# B210B.net
KiCad netlist of a schematic drawn in EAGLE
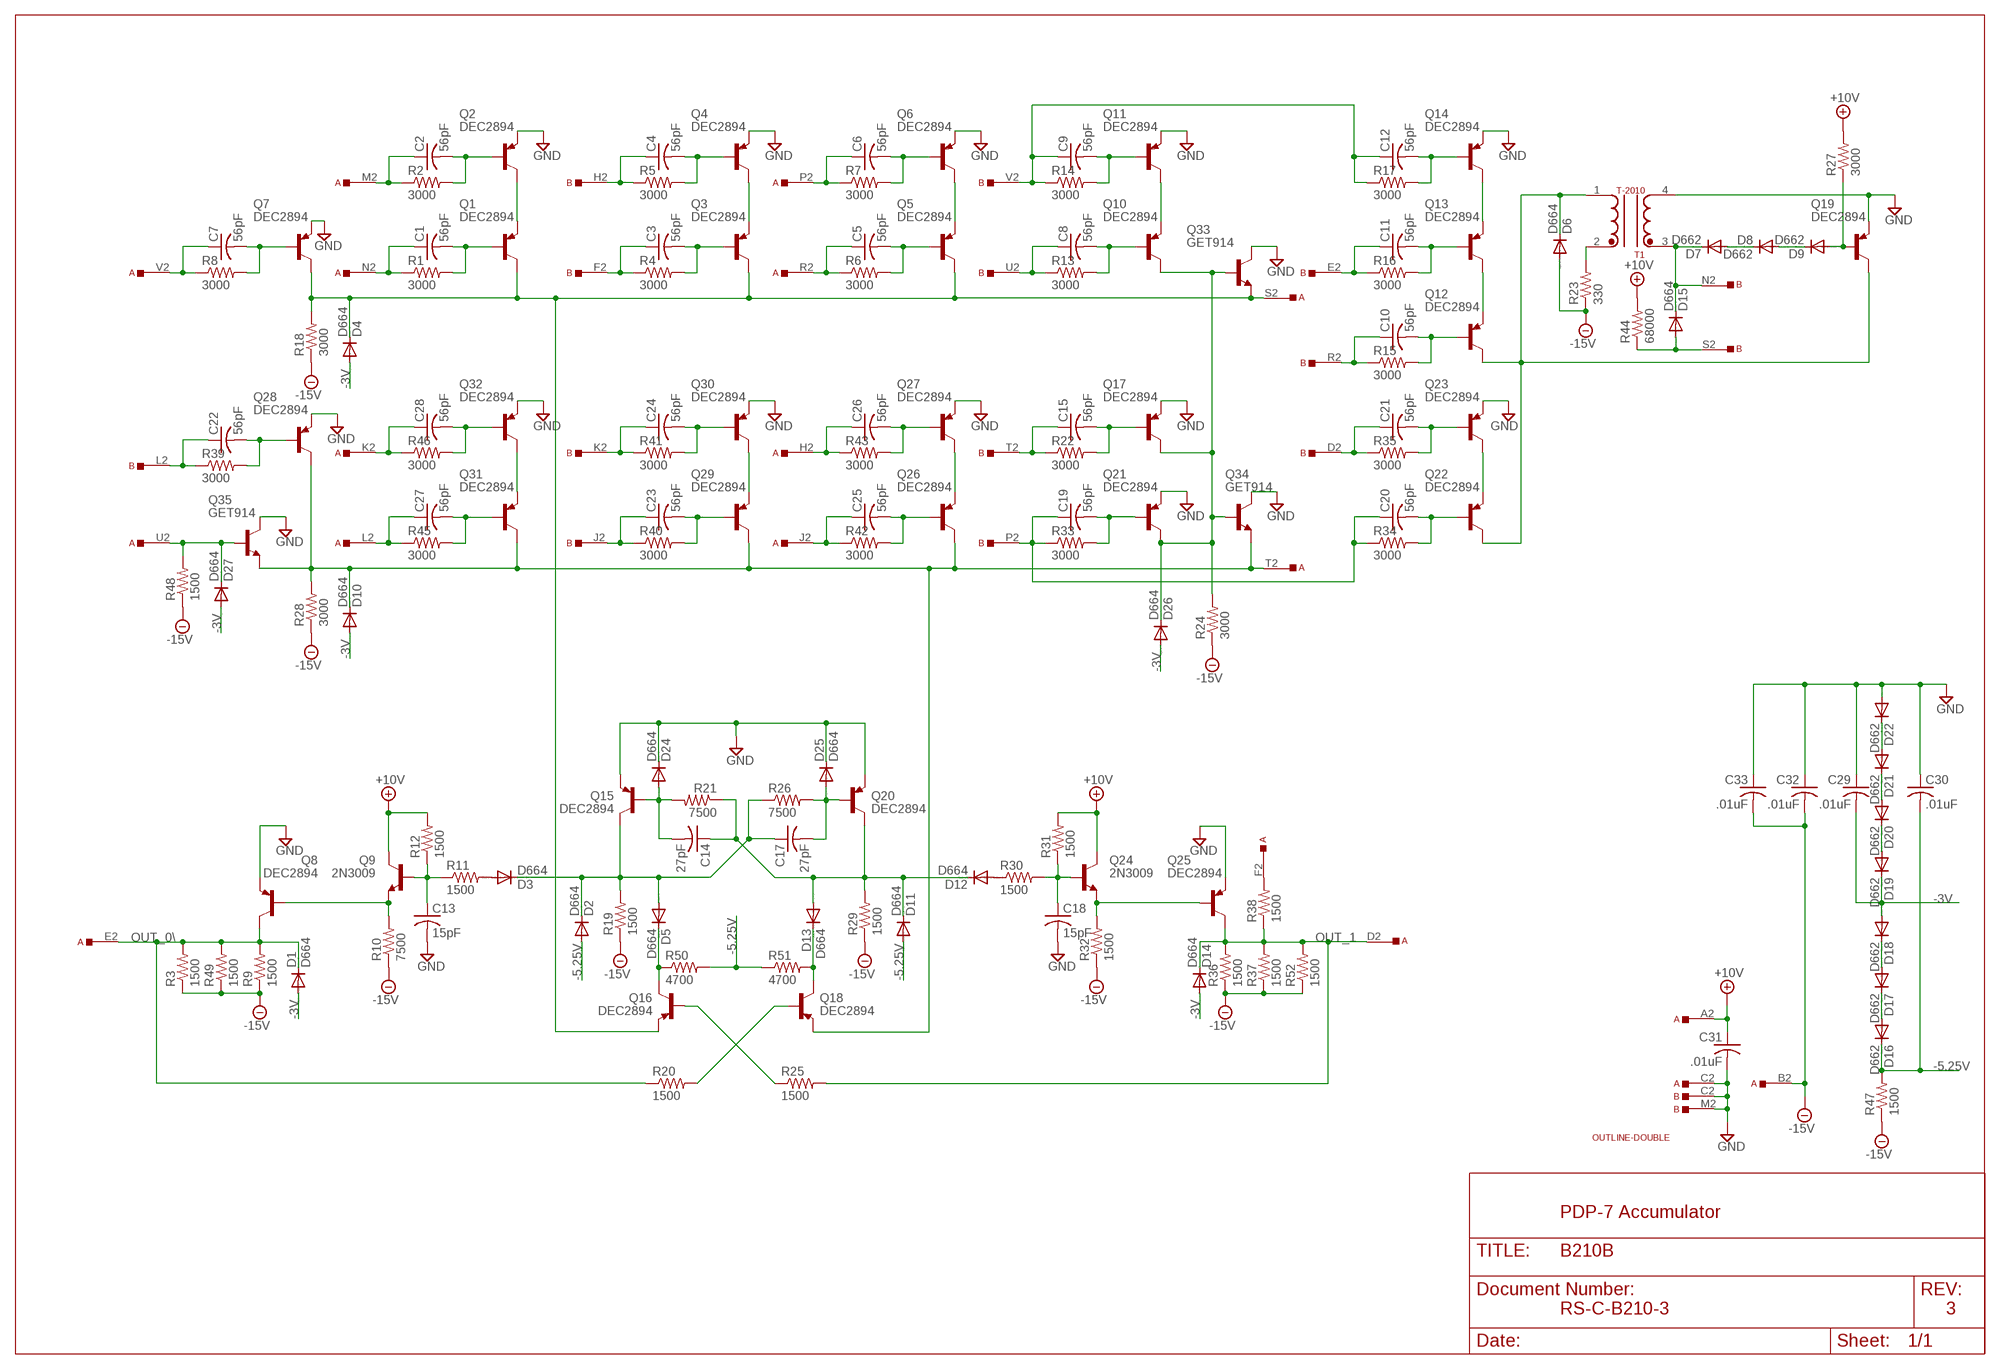
[diagram p0: schematic, sheet 1]

(export (version "E")
  (design (tool "Eeschema 10.0.6"))
  (components
    (comp (ref "A")
      (value "SS-TOP")
      (footprint "eagle-import:EDGE-CON1")
      (libsource (lib "eagle-import") (part "SS-TOP"))
    )
    (comp (ref "B")
      (value "SS-TOP")
      (footprint "eagle-import:EDGE-CON1")
      (libsource (lib "eagle-import") (part "SS-TOP"))
    )
    (comp (ref "C1")
      (value "56pF")
      (footprint "eagle-import:C063-025X075")
      (libsource (lib "eagle-import") (part "C-US"))
    )
    (comp (ref "C2")
      (value "56pF")
      (footprint "eagle-import:C063-025X075")
      (libsource (lib "eagle-import") (part "C-US"))
    )
    (comp (ref "C3")
      (value "56pF")
      (footprint "eagle-import:C063-025X075")
      (libsource (lib "eagle-import") (part "C-US"))
    )
    (comp (ref "C4")
      (value "56pF")
      (footprint "eagle-import:C063-025X075")
      (libsource (lib "eagle-import") (part "C-US"))
    )
    (comp (ref "C5")
      (value "56pF")
      (footprint "eagle-import:C063-025X075")
      (libsource (lib "eagle-import") (part "C-US"))
    )
    (comp (ref "C6")
      (value "56pF")
      (footprint "eagle-import:C063-025X075")
      (libsource (lib "eagle-import") (part "C-US"))
    )
    (comp (ref "C7")
      (value "56pF")
      (footprint "eagle-import:C063-025X075")
      (libsource (lib "eagle-import") (part "C-US"))
    )
    (comp (ref "C8")
      (value "56pF")
      (footprint "eagle-import:C063-025X075")
      (libsource (lib "eagle-import") (part "C-US"))
    )
    (comp (ref "C9")
      (value "56pF")
      (footprint "eagle-import:C063-025X075")
      (libsource (lib "eagle-import") (part "C-US"))
    )
    (comp (ref "C10")
      (value "56pF")
      (footprint "eagle-import:C063-025X075")
      (libsource (lib "eagle-import") (part "C-US"))
    )
    (comp (ref "C11")
      (value "56pF")
      (footprint "eagle-import:C063-025X075")
      (libsource (lib "eagle-import") (part "C-US"))
    )
    (comp (ref "C12")
      (value "56pF")
      (footprint "eagle-import:C063-025X075")
      (libsource (lib "eagle-import") (part "C-US"))
    )
    (comp (ref "C13")
      (value "15pF")
      (footprint "eagle-import:C063-025X075")
      (libsource (lib "eagle-import") (part "C-US"))
    )
    (comp (ref "C14")
      (value "27pF")
      (footprint "eagle-import:C063-025X075")
      (libsource (lib "eagle-import") (part "C-US"))
    )
    (comp (ref "C15")
      (value "56pF")
      (footprint "eagle-import:C063-025X075")
      (libsource (lib "eagle-import") (part "C-US"))
    )
    (comp (ref "C17")
      (value "27pF")
      (footprint "eagle-import:C063-025X075")
      (libsource (lib "eagle-import") (part "C-US"))
    )
    (comp (ref "C18")
      (value "15pF")
      (footprint "eagle-import:C063-025X075")
      (libsource (lib "eagle-import") (part "C-US"))
    )
    (comp (ref "C19")
      (value "56pF")
      (footprint "eagle-import:C063-025X075")
      (libsource (lib "eagle-import") (part "C-US"))
    )
    (comp (ref "C20")
      (value "56pF")
      (footprint "eagle-import:C063-025X075")
      (libsource (lib "eagle-import") (part "C-US"))
    )
    (comp (ref "C21")
      (value "56pF")
      (footprint "eagle-import:C063-025X075")
      (libsource (lib "eagle-import") (part "C-US"))
    )
    (comp (ref "C22")
      (value "56pF")
      (footprint "eagle-import:C063-025X075")
      (libsource (lib "eagle-import") (part "C-US"))
    )
    (comp (ref "C23")
      (value "56pF")
      (footprint "eagle-import:C063-025X075")
      (libsource (lib "eagle-import") (part "C-US"))
    )
    (comp (ref "C24")
      (value "56pF")
      (footprint "eagle-import:C063-025X075")
      (libsource (lib "eagle-import") (part "C-US"))
    )
    (comp (ref "C25")
      (value "56pF")
      (footprint "eagle-import:C063-025X075")
      (libsource (lib "eagle-import") (part "C-US"))
    )
    (comp (ref "C26")
      (value "56pF")
      (footprint "eagle-import:C063-025X075")
      (libsource (lib "eagle-import") (part "C-US"))
    )
    (comp (ref "C27")
      (value "56pF")
      (footprint "eagle-import:C063-025X075")
      (libsource (lib "eagle-import") (part "C-US"))
    )
    (comp (ref "C28")
      (value "56pF")
      (footprint "eagle-import:C063-025X075")
      (libsource (lib "eagle-import") (part "C-US"))
    )
    (comp (ref "C29")
      (value ".01uF")
      (footprint "eagle-import:C063-025X075")
      (libsource (lib "eagle-import") (part "C-US"))
    )
    (comp (ref "C30")
      (value ".01uF")
      (footprint "eagle-import:C063-025X075")
      (libsource (lib "eagle-import") (part "C-US"))
    )
    (comp (ref "C31")
      (value ".01uF")
      (footprint "eagle-import:C063-025X075")
      (libsource (lib "eagle-import") (part "C-US"))
    )
    (comp (ref "C32")
      (value ".01uF")
      (footprint "eagle-import:C063-025X075")
      (libsource (lib "eagle-import") (part "C-US"))
    )
    (comp (ref "C33")
      (value ".01uF")
      (footprint "eagle-import:C063-025X075")
      (libsource (lib "eagle-import") (part "C-US"))
    )
    (comp (ref "D1")
      (value "D664")
      (footprint "eagle-import:DO35-10")
      (libsource (lib "eagle-import") (part "DIODE-DO35-10"))
    )
    (comp (ref "D2")
      (value "D664")
      (footprint "eagle-import:DO35-10")
      (libsource (lib "eagle-import") (part "DIODE-DO35-10"))
    )
    (comp (ref "D3")
      (value "D664")
      (footprint "eagle-import:DO35-10")
      (libsource (lib "eagle-import") (part "DIODE-DO35-10"))
    )
    (comp (ref "D4")
      (value "D664")
      (footprint "eagle-import:DO35-10")
      (libsource (lib "eagle-import") (part "DIODE-DO35-10"))
    )
    (comp (ref "D5")
      (value "D664")
      (footprint "eagle-import:DO35-10")
      (libsource (lib "eagle-import") (part "DIODE-DO35-10"))
    )
    (comp (ref "D6")
      (value "D664")
      (footprint "eagle-import:DO35-10")
      (libsource (lib "eagle-import") (part "DIODE-DO35-10"))
    )
    (comp (ref "D7")
      (value "D662")
      (footprint "eagle-import:DO35-10")
      (libsource (lib "eagle-import") (part "DIODE-DO35-10"))
    )
    (comp (ref "D8")
      (value "D662")
      (footprint "eagle-import:DO35-10")
      (libsource (lib "eagle-import") (part "DIODE-DO35-10"))
    )
    (comp (ref "D9")
      (value "D662")
      (footprint "eagle-import:DO35-10")
      (libsource (lib "eagle-import") (part "DIODE-DO35-10"))
    )
    (comp (ref "D10")
      (value "D664")
      (footprint "eagle-import:DO35-10")
      (libsource (lib "eagle-import") (part "DIODE-DO35-10"))
    )
    (comp (ref "D11")
      (value "D664")
      (footprint "eagle-import:DO35-10")
      (libsource (lib "eagle-import") (part "DIODE-DO35-10"))
    )
    (comp (ref "D12")
      (value "D664")
      (footprint "eagle-import:DO35-10")
      (libsource (lib "eagle-import") (part "DIODE-DO35-10"))
    )
    (comp (ref "D13")
      (value "D664")
      (footprint "eagle-import:DO35-10")
      (libsource (lib "eagle-import") (part "DIODE-DO35-10"))
    )
    (comp (ref "D14")
      (value "D664")
      (footprint "eagle-import:DO35-10")
      (libsource (lib "eagle-import") (part "DIODE-DO35-10"))
    )
    (comp (ref "D15")
      (value "D664")
      (footprint "eagle-import:DO35-10")
      (libsource (lib "eagle-import") (part "DIODE-DO35-10"))
    )
    (comp (ref "D16")
      (value "D662")
      (footprint "eagle-import:DO35-10")
      (libsource (lib "eagle-import") (part "DIODE-DO35-10"))
    )
    (comp (ref "D17")
      (value "D662")
      (footprint "eagle-import:DO35-10")
      (libsource (lib "eagle-import") (part "DIODE-DO35-10"))
    )
    (comp (ref "D18")
      (value "D662")
      (footprint "eagle-import:DO35-10")
      (libsource (lib "eagle-import") (part "DIODE-DO35-10"))
    )
    (comp (ref "D19")
      (value "D662")
      (footprint "eagle-import:DO35-10")
      (libsource (lib "eagle-import") (part "DIODE-DO35-10"))
    )
    (comp (ref "D20")
      (value "D662")
      (footprint "eagle-import:DO35-10")
      (libsource (lib "eagle-import") (part "DIODE-DO35-10"))
    )
    (comp (ref "D21")
      (value "D662")
      (footprint "eagle-import:DO35-10")
      (libsource (lib "eagle-import") (part "DIODE-DO35-10"))
    )
    (comp (ref "D22")
      (value "D662")
      (footprint "eagle-import:DO35-10")
      (libsource (lib "eagle-import") (part "DIODE-DO35-10"))
    )
    (comp (ref "D24")
      (value "D664")
      (footprint "eagle-import:DO35-10")
      (libsource (lib "eagle-import") (part "DIODE-DO35-10"))
    )
    (comp (ref "D25")
      (value "D664")
      (footprint "eagle-import:DO35-10")
      (libsource (lib "eagle-import") (part "DIODE-DO35-10"))
    )
    (comp (ref "D26")
      (value "D664")
      (footprint "eagle-import:DO35-10")
      (libsource (lib "eagle-import") (part "DIODE-DO35-10"))
    )
    (comp (ref "D27")
      (value "D664")
      (footprint "eagle-import:DO35-10")
      (libsource (lib "eagle-import") (part "DIODE-DO35-10"))
    )
    (comp (ref "Q1")
      (value "DEC2894")
      (footprint "eagle-import:TO5")
      (libsource (lib "eagle-import") (part "-PNP-TO5"))
    )
    (comp (ref "Q2")
      (value "DEC2894")
      (footprint "eagle-import:TO5")
      (libsource (lib "eagle-import") (part "-PNP-TO5"))
    )
    (comp (ref "Q3")
      (value "DEC2894")
      (footprint "eagle-import:TO5")
      (libsource (lib "eagle-import") (part "-PNP-TO5"))
    )
    (comp (ref "Q4")
      (value "DEC2894")
      (footprint "eagle-import:TO5")
      (libsource (lib "eagle-import") (part "-PNP-TO5"))
    )
    (comp (ref "Q5")
      (value "DEC2894")
      (footprint "eagle-import:TO5")
      (libsource (lib "eagle-import") (part "-PNP-TO5"))
    )
    (comp (ref "Q6")
      (value "DEC2894")
      (footprint "eagle-import:TO5")
      (libsource (lib "eagle-import") (part "-PNP-TO5"))
    )
    (comp (ref "Q7")
      (value "DEC2894")
      (footprint "eagle-import:TO5")
      (libsource (lib "eagle-import") (part "-PNP-TO5"))
    )
    (comp (ref "Q8")
      (value "DEC2894")
      (footprint "eagle-import:TO5")
      (libsource (lib "eagle-import") (part "-PNP-TO5"))
    )
    (comp (ref "Q9")
      (value "2N3009")
      (footprint "eagle-import:TO5")
      (libsource (lib "eagle-import") (part "-NPN-TO5"))
    )
    (comp (ref "Q10")
      (value "DEC2894")
      (footprint "eagle-import:TO5")
      (libsource (lib "eagle-import") (part "-PNP-TO5"))
    )
    (comp (ref "Q11")
      (value "DEC2894")
      (footprint "eagle-import:TO5")
      (libsource (lib "eagle-import") (part "-PNP-TO5"))
    )
    (comp (ref "Q12")
      (value "DEC2894")
      (footprint "eagle-import:TO5")
      (libsource (lib "eagle-import") (part "-PNP-TO5"))
    )
    (comp (ref "Q13")
      (value "DEC2894")
      (footprint "eagle-import:TO5")
      (libsource (lib "eagle-import") (part "-PNP-TO5"))
    )
    (comp (ref "Q14")
      (value "DEC2894")
      (footprint "eagle-import:TO5")
      (libsource (lib "eagle-import") (part "-PNP-TO5"))
    )
    (comp (ref "Q15")
      (value "DEC2894")
      (footprint "eagle-import:TO5")
      (libsource (lib "eagle-import") (part "-PNP-TO5"))
    )
    (comp (ref "Q16")
      (value "DEC2894")
      (footprint "eagle-import:TO5")
      (libsource (lib "eagle-import") (part "-PNP-TO5"))
    )
    (comp (ref "Q17")
      (value "DEC2894")
      (footprint "eagle-import:TO5")
      (libsource (lib "eagle-import") (part "-PNP-TO5"))
    )
    (comp (ref "Q18")
      (value "DEC2894")
      (footprint "eagle-import:TO5")
      (libsource (lib "eagle-import") (part "-PNP-TO5"))
    )
    (comp (ref "Q19")
      (value "DEC2894")
      (footprint "eagle-import:TO5")
      (libsource (lib "eagle-import") (part "-PNP-TO5"))
    )
    (comp (ref "Q20")
      (value "DEC2894")
      (footprint "eagle-import:TO5")
      (libsource (lib "eagle-import") (part "-PNP-TO5"))
    )
    (comp (ref "Q21")
      (value "DEC2894")
      (footprint "eagle-import:TO5")
      (libsource (lib "eagle-import") (part "-PNP-TO5"))
    )
    (comp (ref "Q22")
      (value "DEC2894")
      (footprint "eagle-import:TO5")
      (libsource (lib "eagle-import") (part "-PNP-TO5"))
    )
    (comp (ref "Q23")
      (value "DEC2894")
      (footprint "eagle-import:TO5")
      (libsource (lib "eagle-import") (part "-PNP-TO5"))
    )
    (comp (ref "Q24")
      (value "2N3009")
      (footprint "eagle-import:TO5")
      (libsource (lib "eagle-import") (part "-NPN-TO5"))
    )
    (comp (ref "Q25")
      (value "DEC2894")
      (footprint "eagle-import:TO5")
      (libsource (lib "eagle-import") (part "-PNP-TO5"))
    )
    (comp (ref "Q26")
      (value "DEC2894")
      (footprint "eagle-import:TO5")
      (libsource (lib "eagle-import") (part "-PNP-TO5"))
    )
    (comp (ref "Q27")
      (value "DEC2894")
      (footprint "eagle-import:TO5")
      (libsource (lib "eagle-import") (part "-PNP-TO5"))
    )
    (comp (ref "Q28")
      (value "DEC2894")
      (footprint "eagle-import:TO5")
      (libsource (lib "eagle-import") (part "-PNP-TO5"))
    )
    (comp (ref "Q29")
      (value "DEC2894")
      (footprint "eagle-import:TO5")
      (libsource (lib "eagle-import") (part "-PNP-TO5"))
    )
    (comp (ref "Q30")
      (value "DEC2894")
      (footprint "eagle-import:TO5")
      (libsource (lib "eagle-import") (part "-PNP-TO5"))
    )
    (comp (ref "Q31")
      (value "DEC2894")
      (footprint "eagle-import:TO5")
      (libsource (lib "eagle-import") (part "-PNP-TO5"))
    )
    (comp (ref "Q32")
      (value "DEC2894")
      (footprint "eagle-import:TO5")
      (libsource (lib "eagle-import") (part "-PNP-TO5"))
    )
    (comp (ref "Q33")
      (value "GET914")
      (footprint "eagle-import:TO5")
      (libsource (lib "eagle-import") (part "-NPN-TO5"))
    )
    (comp (ref "Q34")
      (value "GET914")
      (footprint "eagle-import:TO5")
      (libsource (lib "eagle-import") (part "-NPN-TO5"))
    )
    (comp (ref "Q35")
      (value "GET914")
      (footprint "eagle-import:TO5")
      (libsource (lib "eagle-import") (part "-NPN-TO5"))
    )
    (comp (ref "R1")
      (value "3000")
      (footprint "eagle-import:0207_10")
      (libsource (lib "eagle-import") (part "R-US_0207/10"))
    )
    (comp (ref "R2")
      (value "3000")
      (footprint "eagle-import:0207_10")
      (libsource (lib "eagle-import") (part "R-US_0207/10"))
    )
    (comp (ref "R3")
      (value "1500")
      (footprint "eagle-import:0207_10")
      (libsource (lib "eagle-import") (part "R-US_0207/10"))
    )
    (comp (ref "R4")
      (value "3000")
      (footprint "eagle-import:0207_10")
      (libsource (lib "eagle-import") (part "R-US_0207/10"))
    )
    (comp (ref "R5")
      (value "3000")
      (footprint "eagle-import:0207_10")
      (libsource (lib "eagle-import") (part "R-US_0207/10"))
    )
    (comp (ref "R6")
      (value "3000")
      (footprint "eagle-import:0207_10")
      (libsource (lib "eagle-import") (part "R-US_0207/10"))
    )
    (comp (ref "R7")
      (value "3000")
      (footprint "eagle-import:0207_10")
      (libsource (lib "eagle-import") (part "R-US_0207/10"))
    )
    (comp (ref "R8")
      (value "3000")
      (footprint "eagle-import:0207_10")
      (libsource (lib "eagle-import") (part "R-US_0207/10"))
    )
    (comp (ref "R9")
      (value "1500")
      (footprint "eagle-import:0207_10")
      (libsource (lib "eagle-import") (part "R-US_0207/10"))
    )
    (comp (ref "R10")
      (value "7500")
      (footprint "eagle-import:0207_10")
      (libsource (lib "eagle-import") (part "R-US_0207/10"))
    )
    (comp (ref "R11")
      (value "1500")
      (footprint "eagle-import:0207_10")
      (libsource (lib "eagle-import") (part "R-US_0207/10"))
    )
    (comp (ref "R12")
      (value "1500")
      (footprint "eagle-import:0207_10")
      (libsource (lib "eagle-import") (part "R-US_0207/10"))
    )
    (comp (ref "R13")
      (value "3000")
      (footprint "eagle-import:0207_10")
      (libsource (lib "eagle-import") (part "R-US_0207/10"))
    )
    (comp (ref "R14")
      (value "3000")
      (footprint "eagle-import:0207_10")
      (libsource (lib "eagle-import") (part "R-US_0207/10"))
    )
    (comp (ref "R15")
      (value "3000")
      (footprint "eagle-import:0207_10")
      (libsource (lib "eagle-import") (part "R-US_0207/10"))
    )
    (comp (ref "R16")
      (value "3000")
      (footprint "eagle-import:0207_10")
      (libsource (lib "eagle-import") (part "R-US_0207/10"))
    )
    (comp (ref "R17")
      (value "3000")
      (footprint "eagle-import:0207_10")
      (libsource (lib "eagle-import") (part "R-US_0207/10"))
    )
    (comp (ref "R18")
      (value "3000")
      (footprint "eagle-import:0207_10")
      (libsource (lib "eagle-import") (part "R-US_0207/10"))
    )
    (comp (ref "R19")
      (value "1500")
      (footprint "eagle-import:0207_10")
      (libsource (lib "eagle-import") (part "R-US_0207/10"))
    )
    (comp (ref "R20")
      (value "1500")
      (footprint "eagle-import:0207_10")
      (libsource (lib "eagle-import") (part "R-US_0207/10"))
    )
    (comp (ref "R21")
      (value "7500")
      (footprint "eagle-import:0207_10")
      (libsource (lib "eagle-import") (part "R-US_0207/10"))
    )
    (comp (ref "R22")
      (value "3000")
      (footprint "eagle-import:0207_10")
      (libsource (lib "eagle-import") (part "R-US_0207/10"))
    )
    (comp (ref "R23")
      (value "330")
      (footprint "eagle-import:0207_10")
      (libsource (lib "eagle-import") (part "R-US_0207/10"))
    )
    (comp (ref "R24")
      (value "3000")
      (footprint "eagle-import:0207_10")
      (libsource (lib "eagle-import") (part "R-US_0207/10"))
    )
    (comp (ref "R25")
      (value "1500")
      (footprint "eagle-import:0207_10")
      (libsource (lib "eagle-import") (part "R-US_0207/10"))
    )
    (comp (ref "R26")
      (value "7500")
      (footprint "eagle-import:0207_10")
      (libsource (lib "eagle-import") (part "R-US_0207/10"))
    )
    (comp (ref "R27")
      (value "3000")
      (footprint "eagle-import:0207_10")
      (libsource (lib "eagle-import") (part "R-US_0207/10"))
    )
    (comp (ref "R28")
      (value "3000")
      (footprint "eagle-import:0207_10")
      (libsource (lib "eagle-import") (part "R-US_0207/10"))
    )
    (comp (ref "R29")
      (value "1500")
      (footprint "eagle-import:0207_10")
      (libsource (lib "eagle-import") (part "R-US_0207/10"))
    )
    (comp (ref "R30")
      (value "1500")
      (footprint "eagle-import:0207_10")
      (libsource (lib "eagle-import") (part "R-US_0207/10"))
    )
    (comp (ref "R31")
      (value "1500")
      (footprint "eagle-import:0207_10")
      (libsource (lib "eagle-import") (part "R-US_0207/10"))
    )
    (comp (ref "R32")
      (value "1500")
      (footprint "eagle-import:0207_10")
      (libsource (lib "eagle-import") (part "R-US_0207/10"))
    )
    (comp (ref "R33")
      (value "3000")
      (footprint "eagle-import:0207_10")
      (libsource (lib "eagle-import") (part "R-US_0207/10"))
    )
    (comp (ref "R34")
      (value "3000")
      (footprint "eagle-import:0207_10")
      (libsource (lib "eagle-import") (part "R-US_0207/10"))
    )
    (comp (ref "R35")
      (value "3000")
      (footprint "eagle-import:0207_10")
      (libsource (lib "eagle-import") (part "R-US_0207/10"))
    )
    (comp (ref "R36")
      (value "1500")
      (footprint "eagle-import:0207_10")
      (libsource (lib "eagle-import") (part "R-US_0207/10"))
    )
    (comp (ref "R37")
      (value "1500")
      (footprint "eagle-import:0207_10")
      (libsource (lib "eagle-import") (part "R-US_0207/10"))
    )
    (comp (ref "R38")
      (value "1500")
      (footprint "eagle-import:0207_10")
      (libsource (lib "eagle-import") (part "R-US_0207/10"))
    )
    (comp (ref "R39")
      (value "3000")
      (footprint "eagle-import:0207_10")
      (libsource (lib "eagle-import") (part "R-US_0207/10"))
    )
    (comp (ref "R40")
      (value "3000")
      (footprint "eagle-import:0207_10")
      (libsource (lib "eagle-import") (part "R-US_0207/10"))
    )
    (comp (ref "R41")
      (value "3000")
      (footprint "eagle-import:0207_10")
      (libsource (lib "eagle-import") (part "R-US_0207/10"))
    )
    (comp (ref "R42")
      (value "3000")
      (footprint "eagle-import:0207_10")
      (libsource (lib "eagle-import") (part "R-US_0207/10"))
    )
    (comp (ref "R43")
      (value "3000")
      (footprint "eagle-import:0207_10")
      (libsource (lib "eagle-import") (part "R-US_0207/10"))
    )
    (comp (ref "R44")
      (value "68000")
      (footprint "eagle-import:0207_10")
      (libsource (lib "eagle-import") (part "R-US_0207/10"))
    )
    (comp (ref "R45")
      (value "3000")
      (footprint "eagle-import:0207_10")
      (libsource (lib "eagle-import") (part "R-US_0207/10"))
    )
    (comp (ref "R46")
      (value "3000")
      (footprint "eagle-import:0207_10")
      (libsource (lib "eagle-import") (part "R-US_0207/10"))
    )
    (comp (ref "R47")
      (value "1500")
      (footprint "eagle-import:0207_10")
      (libsource (lib "eagle-import") (part "R-US_0207/10"))
    )
    (comp (ref "R48")
      (value "1500")
      (footprint "eagle-import:0207_10")
      (libsource (lib "eagle-import") (part "R-US_0207/10"))
    )
    (comp (ref "R49")
      (value "1500")
      (footprint "eagle-import:0207_10")
      (libsource (lib "eagle-import") (part "R-US_0207/10"))
    )
    (comp (ref "R50")
      (value "4700")
      (footprint "eagle-import:0207_10")
      (libsource (lib "eagle-import") (part "R-US_0207/10"))
    )
    (comp (ref "R51")
      (value "4700")
      (footprint "eagle-import:0207_10")
      (libsource (lib "eagle-import") (part "R-US_0207/10"))
    )
    (comp (ref "R52")
      (value "1500")
      (footprint "eagle-import:0207_10")
      (libsource (lib "eagle-import") (part "R-US_0207/10"))
    )
    (comp (ref "T1")
      (value "T-2010")
      (footprint "eagle-import:TRANSFORMER2")
      (libsource (lib "eagle-import") (part "T-2010"))
    )
    (comp (ref "U$1")
      (value "OUTLINE-DOUBLE")
      (footprint "eagle-import:DOUBLE")
      (libsource (lib "eagle-import") (part "OUTLINE-DOUBLE"))
    )
  )
  (nets
    (net (code "1") (name "+10V") (class "Default")
      (node (ref "A") (pin "A2") (pinfunction "P_A2") (pintype "passive"))
      (node (ref "C31") (pin "1") (pinfunction "1_1") (pintype "passive"))
      (node (ref "Q24") (pin "3") (pinfunction "C_3") (pintype "passive"))
      (node (ref "Q9") (pin "3") (pinfunction "C_3") (pintype "passive"))
      (node (ref "R12") (pin "2") (pinfunction "2_2") (pintype "passive"))
      (node (ref "R27") (pin "2") (pinfunction "2_2") (pintype "passive"))
      (node (ref "R31") (pin "2") (pinfunction "2_2") (pintype "passive"))
      (node (ref "R44") (pin "2") (pinfunction "2_2") (pintype "passive"))
    )
    (net (code "2") (name "-15V") (class "Default")
      (node (ref "A") (pin "B2") (pinfunction "P_B2") (pintype "passive"))
      (node (ref "C32") (pin "2") (pinfunction "2_2") (pintype "passive"))
      (node (ref "C33") (pin "2") (pinfunction "2_2") (pintype "passive"))
      (node (ref "D6") (pin "A") (pinfunction "A_A") (pintype "passive"))
      (node (ref "R10") (pin "1") (pinfunction "1_1") (pintype "passive"))
      (node (ref "R18") (pin "1") (pinfunction "1_1") (pintype "passive"))
      (node (ref "R19") (pin "1") (pinfunction "1_1") (pintype "passive"))
      (node (ref "R23") (pin "1") (pinfunction "1_1") (pintype "passive"))
      (node (ref "R24") (pin "1") (pinfunction "1_1") (pintype "passive"))
      (node (ref "R28") (pin "1") (pinfunction "1_1") (pintype "passive"))
      (node (ref "R29") (pin "1") (pinfunction "1_1") (pintype "passive"))
      (node (ref "R3") (pin "1") (pinfunction "1_1") (pintype "passive"))
      (node (ref "R32") (pin "1") (pinfunction "1_1") (pintype "passive"))
      (node (ref "R36") (pin "1") (pinfunction "1_1") (pintype "passive"))
      (node (ref "R37") (pin "1") (pinfunction "1_1") (pintype "passive"))
      (node (ref "R47") (pin "1") (pinfunction "1_1") (pintype "passive"))
      (node (ref "R48") (pin "1") (pinfunction "1_1") (pintype "passive"))
      (node (ref "R49") (pin "1") (pinfunction "1_1") (pintype "passive"))
      (node (ref "R52") (pin "1") (pinfunction "1_1") (pintype "passive"))
      (node (ref "R9") (pin "1") (pinfunction "1_1") (pintype "passive"))
    )
    (net (code "3") (name "/-3V") (class "Default")
      (node (ref "C29") (pin "2") (pinfunction "2_2") (pintype "passive"))
      (node (ref "D1") (pin "A") (pinfunction "A_A") (pintype "passive"))
      (node (ref "D10") (pin "A") (pinfunction "A_A") (pintype "passive"))
      (node (ref "D14") (pin "A") (pinfunction "A_A") (pintype "passive"))
      (node (ref "D18") (pin "A") (pinfunction "A_A") (pintype "passive"))
      (node (ref "D19") (pin "C") (pinfunction "C_C") (pintype "passive"))
      (node (ref "D26") (pin "A") (pinfunction "A_A") (pintype "passive"))
      (node (ref "D27") (pin "A") (pinfunction "A_A") (pintype "passive"))
      (node (ref "D4") (pin "A") (pinfunction "A_A") (pintype "passive"))
    )
    (net (code "4") (name "/-5.25V") (class "Default")
      (node (ref "C30") (pin "2") (pinfunction "2_2") (pintype "passive"))
      (node (ref "D11") (pin "A") (pinfunction "A_A") (pintype "passive"))
      (node (ref "D16") (pin "C") (pinfunction "C_C") (pintype "passive"))
      (node (ref "D2") (pin "A") (pinfunction "A_A") (pintype "passive"))
      (node (ref "R47") (pin "2") (pinfunction "2_2") (pintype "passive"))
      (node (ref "R50") (pin "2") (pinfunction "2_2") (pintype "passive"))
      (node (ref "R51") (pin "1") (pinfunction "1_1") (pintype "passive"))
    )
    (net (code "5") (name "/OUT_0\\") (class "Default")
      (node (ref "A") (pin "E2") (pinfunction "P_E2") (pintype "passive"))
      (node (ref "D1") (pin "C") (pinfunction "C_C") (pintype "passive"))
      (node (ref "Q8") (pin "3") (pinfunction "C_3") (pintype "passive"))
      (node (ref "R20") (pin "1") (pinfunction "1_1") (pintype "passive"))
      (node (ref "R3") (pin "2") (pinfunction "2_2") (pintype "passive"))
      (node (ref "R49") (pin "2") (pinfunction "2_2") (pintype "passive"))
      (node (ref "R9") (pin "2") (pinfunction "2_2") (pintype "passive"))
    )
    (net (code "6") (name "/OUT_1") (class "Default")
      (node (ref "A") (pin "D2") (pinfunction "P_D2") (pintype "passive"))
      (node (ref "D14") (pin "C") (pinfunction "C_C") (pintype "passive"))
      (node (ref "Q25") (pin "3") (pinfunction "C_3") (pintype "passive"))
      (node (ref "R25") (pin "2") (pinfunction "2_2") (pintype "passive"))
      (node (ref "R36") (pin "2") (pinfunction "2_2") (pintype "passive"))
      (node (ref "R37") (pin "2") (pinfunction "2_2") (pintype "passive"))
      (node (ref "R38") (pin "1") (pinfunction "1_1") (pintype "passive"))
      (node (ref "R52") (pin "2") (pinfunction "2_2") (pintype "passive"))
    )
    (net (code "7") (name "GND") (class "Default")
      (node (ref "A") (pin "C2") (pinfunction "P_C2") (pintype "passive"))
      (node (ref "B") (pin "C2") (pinfunction "P_C2") (pintype "passive"))
      (node (ref "B") (pin "M2") (pinfunction "P_M2") (pintype "passive"))
      (node (ref "C13") (pin "2") (pinfunction "2_2") (pintype "passive"))
      (node (ref "C18") (pin "2") (pinfunction "2_2") (pintype "passive"))
      (node (ref "C29") (pin "1") (pinfunction "1_1") (pintype "passive"))
      (node (ref "C30") (pin "1") (pinfunction "1_1") (pintype "passive"))
      (node (ref "C31") (pin "2") (pinfunction "2_2") (pintype "passive"))
      (node (ref "C32") (pin "1") (pinfunction "1_1") (pintype "passive"))
      (node (ref "C33") (pin "1") (pinfunction "1_1") (pintype "passive"))
      (node (ref "D22") (pin "A") (pinfunction "A_A") (pintype "passive"))
      (node (ref "D24") (pin "C") (pinfunction "C_C") (pintype "passive"))
      (node (ref "D25") (pin "C") (pinfunction "C_C") (pintype "passive"))
      (node (ref "Q11") (pin "1") (pinfunction "E_1") (pintype "passive"))
      (node (ref "Q14") (pin "1") (pinfunction "E_1") (pintype "passive"))
      (node (ref "Q15") (pin "1") (pinfunction "E_1") (pintype "passive"))
      (node (ref "Q17") (pin "1") (pinfunction "E_1") (pintype "passive"))
      (node (ref "Q19") (pin "1") (pinfunction "E_1") (pintype "passive"))
      (node (ref "Q2") (pin "1") (pinfunction "E_1") (pintype "passive"))
      (node (ref "Q20") (pin "1") (pinfunction "E_1") (pintype "passive"))
      (node (ref "Q21") (pin "1") (pinfunction "E_1") (pintype "passive"))
      (node (ref "Q23") (pin "1") (pinfunction "E_1") (pintype "passive"))
      (node (ref "Q25") (pin "1") (pinfunction "E_1") (pintype "passive"))
      (node (ref "Q27") (pin "1") (pinfunction "E_1") (pintype "passive"))
      (node (ref "Q28") (pin "1") (pinfunction "E_1") (pintype "passive"))
      (node (ref "Q30") (pin "1") (pinfunction "E_1") (pintype "passive"))
      (node (ref "Q32") (pin "1") (pinfunction "E_1") (pintype "passive"))
      (node (ref "Q33") (pin "3") (pinfunction "C_3") (pintype "passive"))
      (node (ref "Q34") (pin "3") (pinfunction "C_3") (pintype "passive"))
      (node (ref "Q35") (pin "3") (pinfunction "C_3") (pintype "passive"))
      (node (ref "Q4") (pin "1") (pinfunction "E_1") (pintype "passive"))
      (node (ref "Q6") (pin "1") (pinfunction "E_1") (pintype "passive"))
      (node (ref "Q7") (pin "1") (pinfunction "E_1") (pintype "passive"))
      (node (ref "Q8") (pin "1") (pinfunction "E_1") (pintype "passive"))
      (node (ref "T1") (pin "4") (pinfunction "P$7_4") (pintype "passive"))
    )
    (net (code "8") (name "Net-(AF-P)") (class "Default")
      (node (ref "A") (pin "F2") (pinfunction "P_F2") (pintype "passive"))
      (node (ref "R38") (pin "2") (pinfunction "2_2") (pintype "passive"))
    )
    (net (code "9") (name "Net-(AG-P)") (class "Default")
      (node (ref "A") (pin "H2") (pinfunction "P_H2") (pintype "passive"))
      (node (ref "C26") (pin "1") (pinfunction "1_1") (pintype "passive"))
      (node (ref "R43") (pin "1") (pinfunction "1_1") (pintype "passive"))
    )
    (net (code "10") (name "Net-(AH-P)") (class "Default")
      (node (ref "A") (pin "J2") (pinfunction "P_J2") (pintype "passive"))
      (node (ref "C25") (pin "1") (pinfunction "1_1") (pintype "passive"))
      (node (ref "R42") (pin "1") (pinfunction "1_1") (pintype "passive"))
    )
    (net (code "11") (name "Net-(AI-P)") (class "Default")
      (node (ref "A") (pin "K2") (pinfunction "P_K2") (pintype "passive"))
      (node (ref "C28") (pin "1") (pinfunction "1_1") (pintype "passive"))
      (node (ref "R46") (pin "1") (pinfunction "1_1") (pintype "passive"))
    )
    (net (code "12") (name "Net-(AJ-P)") (class "Default")
      (node (ref "A") (pin "L2") (pinfunction "P_L2") (pintype "passive"))
      (node (ref "C27") (pin "1") (pinfunction "1_1") (pintype "passive"))
      (node (ref "R45") (pin "1") (pinfunction "1_1") (pintype "passive"))
    )
    (net (code "13") (name "Net-(AK-P)") (class "Default")
      (node (ref "A") (pin "M2") (pinfunction "P_M2") (pintype "passive"))
      (node (ref "C2") (pin "1") (pinfunction "1_1") (pintype "passive"))
      (node (ref "R2") (pin "1") (pinfunction "1_1") (pintype "passive"))
    )
    (net (code "14") (name "Net-(AL-P)") (class "Default")
      (node (ref "A") (pin "N2") (pinfunction "P_N2") (pintype "passive"))
      (node (ref "C1") (pin "1") (pinfunction "1_1") (pintype "passive"))
      (node (ref "R1") (pin "1") (pinfunction "1_1") (pintype "passive"))
    )
    (net (code "15") (name "Net-(AM-P)") (class "Default")
      (node (ref "A") (pin "P2") (pinfunction "P_P2") (pintype "passive"))
      (node (ref "C6") (pin "1") (pinfunction "1_1") (pintype "passive"))
      (node (ref "R7") (pin "1") (pinfunction "1_1") (pintype "passive"))
    )
    (net (code "16") (name "Net-(AN-P)") (class "Default")
      (node (ref "A") (pin "R2") (pinfunction "P_R2") (pintype "passive"))
      (node (ref "C5") (pin "1") (pinfunction "1_1") (pintype "passive"))
      (node (ref "R6") (pin "1") (pinfunction "1_1") (pintype "passive"))
    )
    (net (code "17") (name "Net-(AO-P)") (class "Default")
      (node (ref "A") (pin "S2") (pinfunction "P_S2") (pintype "passive"))
      (node (ref "D4") (pin "C") (pinfunction "C_C") (pintype "passive"))
      (node (ref "Q1") (pin "3") (pinfunction "C_3") (pintype "passive"))
      (node (ref "Q16") (pin "1") (pinfunction "E_1") (pintype "passive"))
      (node (ref "Q3") (pin "3") (pinfunction "C_3") (pintype "passive"))
      (node (ref "Q33") (pin "1") (pinfunction "E_1") (pintype "passive"))
      (node (ref "Q5") (pin "3") (pinfunction "C_3") (pintype "passive"))
      (node (ref "Q7") (pin "3") (pinfunction "C_3") (pintype "passive"))
      (node (ref "R18") (pin "2") (pinfunction "2_2") (pintype "passive"))
    )
    (net (code "18") (name "Net-(AP-P)") (class "Default")
      (node (ref "A") (pin "T2") (pinfunction "P_T2") (pintype "passive"))
      (node (ref "D10") (pin "C") (pinfunction "C_C") (pintype "passive"))
      (node (ref "Q18") (pin "1") (pinfunction "E_1") (pintype "passive"))
      (node (ref "Q26") (pin "3") (pinfunction "C_3") (pintype "passive"))
      (node (ref "Q28") (pin "3") (pinfunction "C_3") (pintype "passive"))
      (node (ref "Q29") (pin "3") (pinfunction "C_3") (pintype "passive"))
      (node (ref "Q31") (pin "3") (pinfunction "C_3") (pintype "passive"))
      (node (ref "Q34") (pin "1") (pinfunction "E_1") (pintype "passive"))
      (node (ref "Q35") (pin "1") (pinfunction "E_1") (pintype "passive"))
      (node (ref "R28") (pin "2") (pinfunction "2_2") (pintype "passive"))
    )
    (net (code "19") (name "Net-(AQ-P)") (class "Default")
      (node (ref "A") (pin "U2") (pinfunction "P_U2") (pintype "passive"))
      (node (ref "D27") (pin "C") (pinfunction "C_C") (pintype "passive"))
      (node (ref "Q35") (pin "2") (pinfunction "B_2") (pintype "passive"))
      (node (ref "R48") (pin "2") (pinfunction "2_2") (pintype "passive"))
    )
    (net (code "20") (name "Net-(AR-P)") (class "Default")
      (node (ref "A") (pin "V2") (pinfunction "P_V2") (pintype "passive"))
      (node (ref "C7") (pin "1") (pinfunction "1_1") (pintype "passive"))
      (node (ref "R8") (pin "1") (pinfunction "1_1") (pintype "passive"))
    )
    (net (code "21") (name "Net-(BD-P)") (class "Default")
      (node (ref "B") (pin "D2") (pinfunction "P_D2") (pintype "passive"))
      (node (ref "C21") (pin "1") (pinfunction "1_1") (pintype "passive"))
      (node (ref "R35") (pin "1") (pinfunction "1_1") (pintype "passive"))
    )
    (net (code "22") (name "Net-(BE-P)") (class "Default")
      (node (ref "B") (pin "E2") (pinfunction "P_E2") (pintype "passive"))
      (node (ref "C11") (pin "1") (pinfunction "1_1") (pintype "passive"))
      (node (ref "R16") (pin "1") (pinfunction "1_1") (pintype "passive"))
    )
    (net (code "23") (name "Net-(BF-P)") (class "Default")
      (node (ref "B") (pin "F2") (pinfunction "P_F2") (pintype "passive"))
      (node (ref "C3") (pin "1") (pinfunction "1_1") (pintype "passive"))
      (node (ref "R4") (pin "1") (pinfunction "1_1") (pintype "passive"))
    )
    (net (code "24") (name "Net-(BG-P)") (class "Default")
      (node (ref "B") (pin "H2") (pinfunction "P_H2") (pintype "passive"))
      (node (ref "C4") (pin "1") (pinfunction "1_1") (pintype "passive"))
      (node (ref "R5") (pin "1") (pinfunction "1_1") (pintype "passive"))
    )
    (net (code "25") (name "Net-(BH-P)") (class "Default")
      (node (ref "B") (pin "J2") (pinfunction "P_J2") (pintype "passive"))
      (node (ref "C23") (pin "1") (pinfunction "1_1") (pintype "passive"))
      (node (ref "R40") (pin "1") (pinfunction "1_1") (pintype "passive"))
    )
    (net (code "26") (name "Net-(BI-P)") (class "Default")
      (node (ref "B") (pin "K2") (pinfunction "P_K2") (pintype "passive"))
      (node (ref "C24") (pin "1") (pinfunction "1_1") (pintype "passive"))
      (node (ref "R41") (pin "1") (pinfunction "1_1") (pintype "passive"))
    )
    (net (code "27") (name "Net-(BJ-P)") (class "Default")
      (node (ref "B") (pin "L2") (pinfunction "P_L2") (pintype "passive"))
      (node (ref "C22") (pin "1") (pinfunction "1_1") (pintype "passive"))
      (node (ref "R39") (pin "1") (pinfunction "1_1") (pintype "passive"))
    )
    (net (code "28") (name "Net-(BL-P)") (class "Default")
      (node (ref "B") (pin "N2") (pinfunction "P_N2") (pintype "passive"))
      (node (ref "D15") (pin "C") (pinfunction "C_C") (pintype "passive"))
      (node (ref "D7") (pin "C") (pinfunction "C_C") (pintype "passive"))
      (node (ref "T1") (pin "3") (pinfunction "P$2_3") (pintype "passive"))
    )
    (net (code "29") (name "Net-(BM-P)") (class "Default")
      (node (ref "B") (pin "P2") (pinfunction "P_P2") (pintype "passive"))
      (node (ref "C19") (pin "1") (pinfunction "1_1") (pintype "passive"))
      (node (ref "C20") (pin "1") (pinfunction "1_1") (pintype "passive"))
      (node (ref "R33") (pin "1") (pinfunction "1_1") (pintype "passive"))
      (node (ref "R34") (pin "1") (pinfunction "1_1") (pintype "passive"))
    )
    (net (code "30") (name "Net-(BN-P)") (class "Default")
      (node (ref "B") (pin "R2") (pinfunction "P_R2") (pintype "passive"))
      (node (ref "C10") (pin "1") (pinfunction "1_1") (pintype "passive"))
      (node (ref "R15") (pin "1") (pinfunction "1_1") (pintype "passive"))
    )
    (net (code "31") (name "Net-(BO-P)") (class "Default")
      (node (ref "B") (pin "S2") (pinfunction "P_S2") (pintype "passive"))
      (node (ref "D15") (pin "A") (pinfunction "A_A") (pintype "passive"))
      (node (ref "R44") (pin "1") (pinfunction "1_1") (pintype "passive"))
    )
    (net (code "32") (name "Net-(BP-P)") (class "Default")
      (node (ref "B") (pin "T2") (pinfunction "P_T2") (pintype "passive"))
      (node (ref "C15") (pin "1") (pinfunction "1_1") (pintype "passive"))
      (node (ref "R22") (pin "1") (pinfunction "1_1") (pintype "passive"))
    )
    (net (code "33") (name "Net-(BQ-P)") (class "Default")
      (node (ref "B") (pin "U2") (pinfunction "P_U2") (pintype "passive"))
      (node (ref "C8") (pin "1") (pinfunction "1_1") (pintype "passive"))
      (node (ref "R13") (pin "1") (pinfunction "1_1") (pintype "passive"))
    )
    (net (code "34") (name "Net-(BR-P)") (class "Default")
      (node (ref "B") (pin "V2") (pinfunction "P_V2") (pintype "passive"))
      (node (ref "C12") (pin "1") (pinfunction "1_1") (pintype "passive"))
      (node (ref "C9") (pin "1") (pinfunction "1_1") (pintype "passive"))
      (node (ref "R14") (pin "1") (pinfunction "1_1") (pintype "passive"))
      (node (ref "R17") (pin "1") (pinfunction "1_1") (pintype "passive"))
    )
    (net (code "35") (name "Net-(D3-PadA)") (class "Default")
      (node (ref "D3") (pin "A") (pinfunction "A_A") (pintype "passive"))
      (node (ref "R11") (pin "2") (pinfunction "2_2") (pintype "passive"))
    )
    (net (code "36") (name "Net-(D7-PadA)") (class "Default")
      (node (ref "D7") (pin "A") (pinfunction "A_A") (pintype "passive"))
      (node (ref "D8") (pin "C") (pinfunction "C_C") (pintype "passive"))
    )
    (net (code "37") (name "Net-(D8-PadA)") (class "Default")
      (node (ref "D8") (pin "A") (pinfunction "A_A") (pintype "passive"))
      (node (ref "D9") (pin "C") (pinfunction "C_C") (pintype "passive"))
    )
    (net (code "38") (name "Net-(D12-PadA)") (class "Default")
      (node (ref "D12") (pin "A") (pinfunction "A_A") (pintype "passive"))
      (node (ref "R30") (pin "1") (pinfunction "1_1") (pintype "passive"))
    )
    (net (code "39") (name "Net-(D16-PadA)") (class "Default")
      (node (ref "D16") (pin "A") (pinfunction "A_A") (pintype "passive"))
      (node (ref "D17") (pin "C") (pinfunction "C_C") (pintype "passive"))
    )
    (net (code "40") (name "Net-(D17-PadA)") (class "Default")
      (node (ref "D17") (pin "A") (pinfunction "A_A") (pintype "passive"))
      (node (ref "D18") (pin "C") (pinfunction "C_C") (pintype "passive"))
    )
    (net (code "41") (name "Net-(D19-PadA)") (class "Default")
      (node (ref "D19") (pin "A") (pinfunction "A_A") (pintype "passive"))
      (node (ref "D20") (pin "C") (pinfunction "C_C") (pintype "passive"))
    )
    (net (code "42") (name "Net-(D20-PadA)") (class "Default")
      (node (ref "D20") (pin "A") (pinfunction "A_A") (pintype "passive"))
      (node (ref "D21") (pin "C") (pinfunction "C_C") (pintype "passive"))
    )
    (net (code "43") (name "Net-(D21-PadA)") (class "Default")
      (node (ref "D21") (pin "A") (pinfunction "A_A") (pintype "passive"))
      (node (ref "D22") (pin "C") (pinfunction "C_C") (pintype "passive"))
    )
    (net (code "44") (name "Net-(Q1-B)") (class "Default")
      (node (ref "C1") (pin "2") (pinfunction "2_2") (pintype "passive"))
      (node (ref "Q1") (pin "2") (pinfunction "B_2") (pintype "passive"))
      (node (ref "R1") (pin "2") (pinfunction "2_2") (pintype "passive"))
    )
    (net (code "45") (name "Net-(Q1-E)") (class "Default")
      (node (ref "Q1") (pin "1") (pinfunction "E_1") (pintype "passive"))
      (node (ref "Q2") (pin "3") (pinfunction "C_3") (pintype "passive"))
    )
    (net (code "46") (name "Net-(Q2-B)") (class "Default")
      (node (ref "C2") (pin "2") (pinfunction "2_2") (pintype "passive"))
      (node (ref "Q2") (pin "2") (pinfunction "B_2") (pintype "passive"))
      (node (ref "R2") (pin "2") (pinfunction "2_2") (pintype "passive"))
    )
    (net (code "47") (name "Net-(Q3-B)") (class "Default")
      (node (ref "C3") (pin "2") (pinfunction "2_2") (pintype "passive"))
      (node (ref "Q3") (pin "2") (pinfunction "B_2") (pintype "passive"))
      (node (ref "R4") (pin "2") (pinfunction "2_2") (pintype "passive"))
    )
    (net (code "48") (name "Net-(Q3-E)") (class "Default")
      (node (ref "Q3") (pin "1") (pinfunction "E_1") (pintype "passive"))
      (node (ref "Q4") (pin "3") (pinfunction "C_3") (pintype "passive"))
    )
    (net (code "49") (name "Net-(Q4-B)") (class "Default")
      (node (ref "C4") (pin "2") (pinfunction "2_2") (pintype "passive"))
      (node (ref "Q4") (pin "2") (pinfunction "B_2") (pintype "passive"))
      (node (ref "R5") (pin "2") (pinfunction "2_2") (pintype "passive"))
    )
    (net (code "50") (name "Net-(Q5-B)") (class "Default")
      (node (ref "C5") (pin "2") (pinfunction "2_2") (pintype "passive"))
      (node (ref "Q5") (pin "2") (pinfunction "B_2") (pintype "passive"))
      (node (ref "R6") (pin "2") (pinfunction "2_2") (pintype "passive"))
    )
    (net (code "51") (name "Net-(Q5-E)") (class "Default")
      (node (ref "Q5") (pin "1") (pinfunction "E_1") (pintype "passive"))
      (node (ref "Q6") (pin "3") (pinfunction "C_3") (pintype "passive"))
    )
    (net (code "52") (name "Net-(Q6-B)") (class "Default")
      (node (ref "C6") (pin "2") (pinfunction "2_2") (pintype "passive"))
      (node (ref "Q6") (pin "2") (pinfunction "B_2") (pintype "passive"))
      (node (ref "R7") (pin "2") (pinfunction "2_2") (pintype "passive"))
    )
    (net (code "53") (name "Net-(Q7-B)") (class "Default")
      (node (ref "C7") (pin "2") (pinfunction "2_2") (pintype "passive"))
      (node (ref "Q7") (pin "2") (pinfunction "B_2") (pintype "passive"))
      (node (ref "R8") (pin "2") (pinfunction "2_2") (pintype "passive"))
    )
    (net (code "54") (name "Net-(Q8-B)") (class "Default")
      (node (ref "Q8") (pin "2") (pinfunction "B_2") (pintype "passive"))
      (node (ref "Q9") (pin "1") (pinfunction "E_1") (pintype "passive"))
      (node (ref "R10") (pin "2") (pinfunction "2_2") (pintype "passive"))
    )
    (net (code "55") (name "Net-(Q9-B)") (class "Default")
      (node (ref "C13") (pin "1") (pinfunction "1_1") (pintype "passive"))
      (node (ref "Q9") (pin "2") (pinfunction "B_2") (pintype "passive"))
      (node (ref "R11") (pin "1") (pinfunction "1_1") (pintype "passive"))
      (node (ref "R12") (pin "1") (pinfunction "1_1") (pintype "passive"))
    )
    (net (code "56") (name "Net-(Q10-B)") (class "Default")
      (node (ref "C8") (pin "2") (pinfunction "2_2") (pintype "passive"))
      (node (ref "Q10") (pin "2") (pinfunction "B_2") (pintype "passive"))
      (node (ref "R13") (pin "2") (pinfunction "2_2") (pintype "passive"))
    )
    (net (code "57") (name "Net-(Q10-C)") (class "Default")
      (node (ref "D26") (pin "C") (pinfunction "C_C") (pintype "passive"))
      (node (ref "Q10") (pin "3") (pinfunction "C_3") (pintype "passive"))
      (node (ref "Q17") (pin "3") (pinfunction "C_3") (pintype "passive"))
      (node (ref "Q21") (pin "3") (pinfunction "C_3") (pintype "passive"))
      (node (ref "Q33") (pin "2") (pinfunction "B_2") (pintype "passive"))
      (node (ref "Q34") (pin "2") (pinfunction "B_2") (pintype "passive"))
      (node (ref "R24") (pin "2") (pinfunction "2_2") (pintype "passive"))
    )
    (net (code "58") (name "Net-(Q10-E)") (class "Default")
      (node (ref "Q10") (pin "1") (pinfunction "E_1") (pintype "passive"))
      (node (ref "Q11") (pin "3") (pinfunction "C_3") (pintype "passive"))
    )
    (net (code "59") (name "Net-(Q11-B)") (class "Default")
      (node (ref "C9") (pin "2") (pinfunction "2_2") (pintype "passive"))
      (node (ref "Q11") (pin "2") (pinfunction "B_2") (pintype "passive"))
      (node (ref "R14") (pin "2") (pinfunction "2_2") (pintype "passive"))
    )
    (net (code "60") (name "Net-(Q12-B)") (class "Default")
      (node (ref "C10") (pin "2") (pinfunction "2_2") (pintype "passive"))
      (node (ref "Q12") (pin "2") (pinfunction "B_2") (pintype "passive"))
      (node (ref "R15") (pin "2") (pinfunction "2_2") (pintype "passive"))
    )
    (net (code "61") (name "Net-(Q12-C)") (class "Default")
      (node (ref "D6") (pin "C") (pinfunction "C_C") (pintype "passive"))
      (node (ref "Q12") (pin "3") (pinfunction "C_3") (pintype "passive"))
      (node (ref "Q19") (pin "3") (pinfunction "C_3") (pintype "passive"))
      (node (ref "Q22") (pin "3") (pinfunction "C_3") (pintype "passive"))
      (node (ref "T1") (pin "1") (pinfunction "P$5_1") (pintype "passive"))
    )
    (net (code "62") (name "Net-(Q12-E)") (class "Default")
      (node (ref "Q12") (pin "1") (pinfunction "E_1") (pintype "passive"))
      (node (ref "Q13") (pin "3") (pinfunction "C_3") (pintype "passive"))
    )
    (net (code "63") (name "Net-(Q13-B)") (class "Default")
      (node (ref "C11") (pin "2") (pinfunction "2_2") (pintype "passive"))
      (node (ref "Q13") (pin "2") (pinfunction "B_2") (pintype "passive"))
      (node (ref "R16") (pin "2") (pinfunction "2_2") (pintype "passive"))
    )
    (net (code "64") (name "Net-(Q13-E)") (class "Default")
      (node (ref "Q13") (pin "1") (pinfunction "E_1") (pintype "passive"))
      (node (ref "Q14") (pin "3") (pinfunction "C_3") (pintype "passive"))
    )
    (net (code "65") (name "Net-(Q14-B)") (class "Default")
      (node (ref "C12") (pin "2") (pinfunction "2_2") (pintype "passive"))
      (node (ref "Q14") (pin "2") (pinfunction "B_2") (pintype "passive"))
      (node (ref "R17") (pin "2") (pinfunction "2_2") (pintype "passive"))
    )
    (net (code "66") (name "Net-(Q15-B)") (class "Default")
      (node (ref "C14") (pin "2") (pinfunction "2_2") (pintype "passive"))
      (node (ref "D24") (pin "A") (pinfunction "A_A") (pintype "passive"))
      (node (ref "Q15") (pin "2") (pinfunction "B_2") (pintype "passive"))
      (node (ref "R21") (pin "2") (pinfunction "2_2") (pintype "passive"))
    )
    (net (code "67") (name "Net-(Q15-C)") (class "Default")
      (node (ref "C17") (pin "1") (pinfunction "1_1") (pintype "passive"))
      (node (ref "D2") (pin "C") (pinfunction "C_C") (pintype "passive"))
      (node (ref "D3") (pin "C") (pinfunction "C_C") (pintype "passive"))
      (node (ref "D5") (pin "A") (pinfunction "A_A") (pintype "passive"))
      (node (ref "Q15") (pin "3") (pinfunction "C_3") (pintype "passive"))
      (node (ref "R19") (pin "2") (pinfunction "2_2") (pintype "passive"))
      (node (ref "R26") (pin "1") (pinfunction "1_1") (pintype "passive"))
    )
    (net (code "68") (name "Net-(Q16-B)") (class "Default")
      (node (ref "Q16") (pin "2") (pinfunction "B_2") (pintype "passive"))
      (node (ref "R25") (pin "1") (pinfunction "1_1") (pintype "passive"))
    )
    (net (code "69") (name "Net-(Q16-C)") (class "Default")
      (node (ref "D5") (pin "C") (pinfunction "C_C") (pintype "passive"))
      (node (ref "Q16") (pin "3") (pinfunction "C_3") (pintype "passive"))
      (node (ref "R50") (pin "1") (pinfunction "1_1") (pintype "passive"))
    )
    (net (code "70") (name "Net-(Q17-B)") (class "Default")
      (node (ref "C15") (pin "2") (pinfunction "2_2") (pintype "passive"))
      (node (ref "Q17") (pin "2") (pinfunction "B_2") (pintype "passive"))
      (node (ref "R22") (pin "2") (pinfunction "2_2") (pintype "passive"))
    )
    (net (code "71") (name "Net-(Q18-B)") (class "Default")
      (node (ref "Q18") (pin "2") (pinfunction "B_2") (pintype "passive"))
      (node (ref "R20") (pin "2") (pinfunction "2_2") (pintype "passive"))
    )
    (net (code "72") (name "Net-(Q18-C)") (class "Default")
      (node (ref "D13") (pin "C") (pinfunction "C_C") (pintype "passive"))
      (node (ref "Q18") (pin "3") (pinfunction "C_3") (pintype "passive"))
      (node (ref "R51") (pin "2") (pinfunction "2_2") (pintype "passive"))
    )
    (net (code "73") (name "Net-(Q19-B)") (class "Default")
      (node (ref "D9") (pin "A") (pinfunction "A_A") (pintype "passive"))
      (node (ref "Q19") (pin "2") (pinfunction "B_2") (pintype "passive"))
      (node (ref "R27") (pin "1") (pinfunction "1_1") (pintype "passive"))
    )
    (net (code "74") (name "Net-(Q20-B)") (class "Default")
      (node (ref "C17") (pin "2") (pinfunction "2_2") (pintype "passive"))
      (node (ref "D25") (pin "A") (pinfunction "A_A") (pintype "passive"))
      (node (ref "Q20") (pin "2") (pinfunction "B_2") (pintype "passive"))
      (node (ref "R26") (pin "2") (pinfunction "2_2") (pintype "passive"))
    )
    (net (code "75") (name "Net-(Q20-C)") (class "Default")
      (node (ref "C14") (pin "1") (pinfunction "1_1") (pintype "passive"))
      (node (ref "D11") (pin "C") (pinfunction "C_C") (pintype "passive"))
      (node (ref "D12") (pin "C") (pinfunction "C_C") (pintype "passive"))
      (node (ref "D13") (pin "A") (pinfunction "A_A") (pintype "passive"))
      (node (ref "Q20") (pin "3") (pinfunction "C_3") (pintype "passive"))
      (node (ref "R21") (pin "1") (pinfunction "1_1") (pintype "passive"))
      (node (ref "R29") (pin "2") (pinfunction "2_2") (pintype "passive"))
    )
    (net (code "76") (name "Net-(Q21-B)") (class "Default")
      (node (ref "C19") (pin "2") (pinfunction "2_2") (pintype "passive"))
      (node (ref "Q21") (pin "2") (pinfunction "B_2") (pintype "passive"))
      (node (ref "R33") (pin "2") (pinfunction "2_2") (pintype "passive"))
    )
    (net (code "77") (name "Net-(Q22-B)") (class "Default")
      (node (ref "C20") (pin "2") (pinfunction "2_2") (pintype "passive"))
      (node (ref "Q22") (pin "2") (pinfunction "B_2") (pintype "passive"))
      (node (ref "R34") (pin "2") (pinfunction "2_2") (pintype "passive"))
    )
    (net (code "78") (name "Net-(Q22-E)") (class "Default")
      (node (ref "Q22") (pin "1") (pinfunction "E_1") (pintype "passive"))
      (node (ref "Q23") (pin "3") (pinfunction "C_3") (pintype "passive"))
    )
    (net (code "79") (name "Net-(Q23-B)") (class "Default")
      (node (ref "C21") (pin "2") (pinfunction "2_2") (pintype "passive"))
      (node (ref "Q23") (pin "2") (pinfunction "B_2") (pintype "passive"))
      (node (ref "R35") (pin "2") (pinfunction "2_2") (pintype "passive"))
    )
    (net (code "80") (name "Net-(Q24-B)") (class "Default")
      (node (ref "C18") (pin "1") (pinfunction "1_1") (pintype "passive"))
      (node (ref "Q24") (pin "2") (pinfunction "B_2") (pintype "passive"))
      (node (ref "R30") (pin "2") (pinfunction "2_2") (pintype "passive"))
      (node (ref "R31") (pin "1") (pinfunction "1_1") (pintype "passive"))
    )
    (net (code "81") (name "Net-(Q24-E)") (class "Default")
      (node (ref "Q24") (pin "1") (pinfunction "E_1") (pintype "passive"))
      (node (ref "Q25") (pin "2") (pinfunction "B_2") (pintype "passive"))
      (node (ref "R32") (pin "2") (pinfunction "2_2") (pintype "passive"))
    )
    (net (code "82") (name "Net-(Q26-B)") (class "Default")
      (node (ref "C25") (pin "2") (pinfunction "2_2") (pintype "passive"))
      (node (ref "Q26") (pin "2") (pinfunction "B_2") (pintype "passive"))
      (node (ref "R42") (pin "2") (pinfunction "2_2") (pintype "passive"))
    )
    (net (code "83") (name "Net-(Q26-E)") (class "Default")
      (node (ref "Q26") (pin "1") (pinfunction "E_1") (pintype "passive"))
      (node (ref "Q27") (pin "3") (pinfunction "C_3") (pintype "passive"))
    )
    (net (code "84") (name "Net-(Q27-B)") (class "Default")
      (node (ref "C26") (pin "2") (pinfunction "2_2") (pintype "passive"))
      (node (ref "Q27") (pin "2") (pinfunction "B_2") (pintype "passive"))
      (node (ref "R43") (pin "2") (pinfunction "2_2") (pintype "passive"))
    )
    (net (code "85") (name "Net-(Q28-B)") (class "Default")
      (node (ref "C22") (pin "2") (pinfunction "2_2") (pintype "passive"))
      (node (ref "Q28") (pin "2") (pinfunction "B_2") (pintype "passive"))
      (node (ref "R39") (pin "2") (pinfunction "2_2") (pintype "passive"))
    )
    (net (code "86") (name "Net-(Q29-B)") (class "Default")
      (node (ref "C23") (pin "2") (pinfunction "2_2") (pintype "passive"))
      (node (ref "Q29") (pin "2") (pinfunction "B_2") (pintype "passive"))
      (node (ref "R40") (pin "2") (pinfunction "2_2") (pintype "passive"))
    )
    (net (code "87") (name "Net-(Q29-E)") (class "Default")
      (node (ref "Q29") (pin "1") (pinfunction "E_1") (pintype "passive"))
      (node (ref "Q30") (pin "3") (pinfunction "C_3") (pintype "passive"))
    )
    (net (code "88") (name "Net-(Q30-B)") (class "Default")
      (node (ref "C24") (pin "2") (pinfunction "2_2") (pintype "passive"))
      (node (ref "Q30") (pin "2") (pinfunction "B_2") (pintype "passive"))
      (node (ref "R41") (pin "2") (pinfunction "2_2") (pintype "passive"))
    )
    (net (code "89") (name "Net-(Q31-B)") (class "Default")
      (node (ref "C27") (pin "2") (pinfunction "2_2") (pintype "passive"))
      (node (ref "Q31") (pin "2") (pinfunction "B_2") (pintype "passive"))
      (node (ref "R45") (pin "2") (pinfunction "2_2") (pintype "passive"))
    )
    (net (code "90") (name "Net-(Q31-E)") (class "Default")
      (node (ref "Q31") (pin "1") (pinfunction "E_1") (pintype "passive"))
      (node (ref "Q32") (pin "3") (pinfunction "C_3") (pintype "passive"))
    )
    (net (code "91") (name "Net-(Q32-B)") (class "Default")
      (node (ref "C28") (pin "2") (pinfunction "2_2") (pintype "passive"))
      (node (ref "Q32") (pin "2") (pinfunction "B_2") (pintype "passive"))
      (node (ref "R46") (pin "2") (pinfunction "2_2") (pintype "passive"))
    )
    (net (code "92") (name "Net-(T1-P$4)") (class "Default")
      (node (ref "R23") (pin "2") (pinfunction "2_2") (pintype "passive"))
      (node (ref "T1") (pin "2") (pinfunction "P$4_2") (pintype "passive"))
    )
  )
)
